# H-Bridge_Driver.net
KiCad netlist of a schematic drawn in Altium Designer
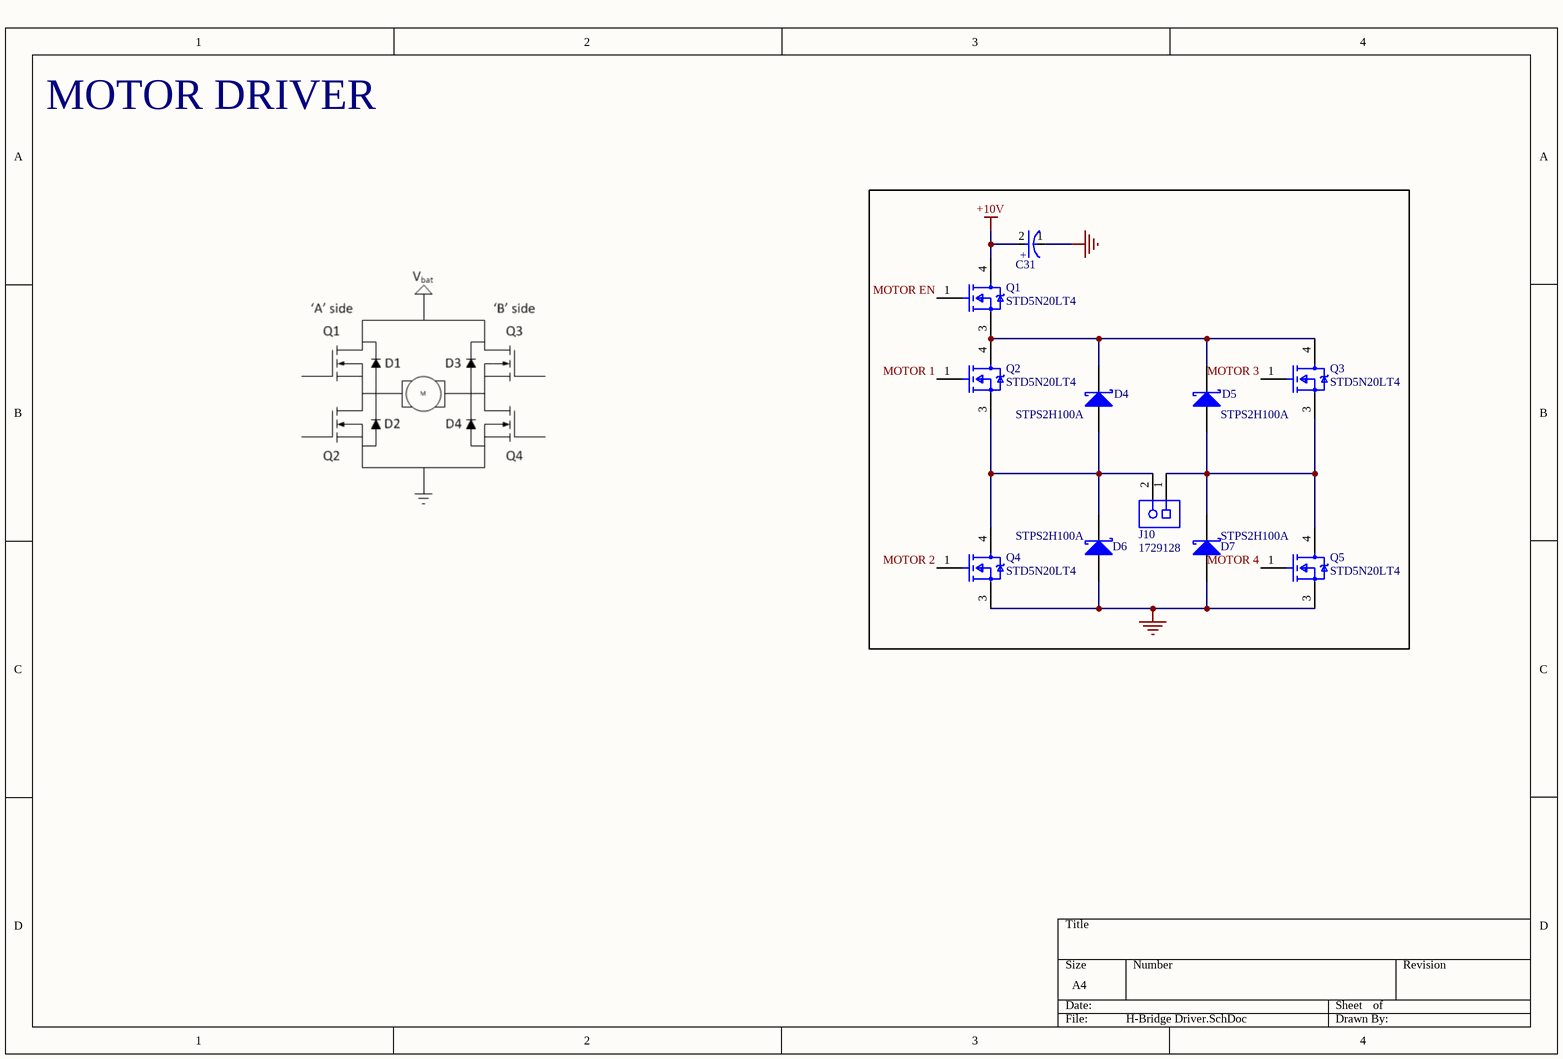
[diagram p0: H-Bridge Driver.SchDoc]

(export (version "E")
  (design (tool "Eeschema 10.0.6"))
  (components
    (comp (ref "C31")
      (value "EEE-1AA102P")
      (footprint "FP-SG-MFG")
      (fields (field (name "VOLTAGE") "10V") (field (name "TOLERANCE") "20%"))
      (libsource (lib "Altium Content Vault") (part "a00bbbee19879c290e62620ae7e47b1"))
    )
    (comp (ref "D4")
      (value "STPS2H100A")
      (footprint "STM-SMA-2_V")
      (description "Power Schottky Rectifier, 2 A, 100 V, 2-Pin SMD (SMA), RoHS, Tape and Reel")
      (fields (field (name "MANUFACTURER") "STMicroelectronics"))
      (libsource (lib "Altium Content Vault") (part "DSKY-AK-2"))
    )
    (comp (ref "D5")
      (value "STPS2H100A")
      (footprint "STM-SMA-2_V")
      (description "Power Schottky Rectifier, 2 A, 100 V, 2-Pin SMD (SMA), RoHS, Tape and Reel")
      (fields (field (name "MANUFACTURER") "STMicroelectronics"))
      (libsource (lib "Altium Content Vault") (part "DSKY-AK-2"))
    )
    (comp (ref "D6")
      (value "STPS2H100A")
      (footprint "STM-SMA-2_V")
      (description "Power Schottky Rectifier, 2 A, 100 V, 2-Pin SMD (SMA), RoHS, Tape and Reel")
      (fields (field (name "MANUFACTURER") "STMicroelectronics"))
      (libsource (lib "Altium Content Vault") (part "DSKY-AK-2"))
    )
    (comp (ref "D7")
      (value "STPS2H100A")
      (footprint "STM-SMA-2_V")
      (description "Power Schottky Rectifier, 2 A, 100 V, 2-Pin SMD (SMA), RoHS, Tape and Reel")
      (fields (field (name "MANUFACTURER") "STMicroelectronics"))
      (libsource (lib "Altium Content Vault") (part "DSKY-AK-2"))
    )
    (comp (ref "J10")
      (value "1729128")
      (footprint "PHOE-1729128-2_V")
      (description "PCB Terminal Block, 13.5 A, 400 V, 2-Pin THD, RoHS, Bulk")
      (fields (field (name "MANUFACTURER") "Phoenix Contact"))
      (libsource (lib "Altium Content Vault") (part "CN-2P-F-R2"))
    )
    (comp (ref "Q1")
      (value "STD5N20LT4")
      (footprint "FP-DPAK-P032P-MFG")
      (description "MOSFET N-CH 200V 5A DPAK")
      (fields
        (field (name "MANUFACTURER") "STMicroelectronics")
        (field (name "OCTOPART") "https://octopart.com/std5n20lt4-stmicroelectronics-335491")
      )
      (libsource (lib "Altium Content Vault") (part "cdf1c68f84cb049e5ebc85739c3fcf6"))
    )
    (comp (ref "Q2")
      (value "STD5N20LT4")
      (footprint "FP-DPAK-P032P-MFG")
      (description "MOSFET N-CH 200V 5A DPAK")
      (fields
        (field (name "MANUFACTURER") "STMicroelectronics")
        (field (name "OCTOPART") "https://octopart.com/std5n20lt4-stmicroelectronics-335491")
      )
      (libsource (lib "Altium Content Vault") (part "cdf1c68f84cb049e5ebc85739c3fcf6"))
    )
    (comp (ref "Q3")
      (value "STD5N20LT4")
      (footprint "FP-DPAK-P032P-MFG")
      (description "MOSFET N-CH 200V 5A DPAK")
      (fields
        (field (name "MANUFACTURER") "STMicroelectronics")
        (field (name "OCTOPART") "https://octopart.com/std5n20lt4-stmicroelectronics-335491")
      )
      (libsource (lib "Altium Content Vault") (part "cdf1c68f84cb049e5ebc85739c3fcf6"))
    )
    (comp (ref "Q4")
      (value "STD5N20LT4")
      (footprint "FP-DPAK-P032P-MFG")
      (description "MOSFET N-CH 200V 5A DPAK")
      (fields
        (field (name "MANUFACTURER") "STMicroelectronics")
        (field (name "OCTOPART") "https://octopart.com/std5n20lt4-stmicroelectronics-335491")
      )
      (libsource (lib "Altium Content Vault") (part "cdf1c68f84cb049e5ebc85739c3fcf6"))
    )
    (comp (ref "Q5")
      (value "STD5N20LT4")
      (footprint "FP-DPAK-P032P-MFG")
      (description "MOSFET N-CH 200V 5A DPAK")
      (fields
        (field (name "MANUFACTURER") "STMicroelectronics")
        (field (name "OCTOPART") "https://octopart.com/std5n20lt4-stmicroelectronics-335491")
      )
      (libsource (lib "Altium Content Vault") (part "cdf1c68f84cb049e5ebc85739c3fcf6"))
    )
  )
  (nets
    (net (code "1") (name "+10V") (class "Default")
      (node (ref "C31") (pin "2") (pinfunction "A_2") (pintype "passive"))
      (node (ref "Q1") (pin "4") (pinfunction "D_4") (pintype "passive"))
    )
    (net (code "2") (name "/MOTOR 1") (class "Default")
      (node (ref "Q2") (pin "1") (pinfunction "G_1") (pintype "passive"))
    )
    (net (code "3") (name "/MOTOR 2") (class "Default")
      (node (ref "Q4") (pin "1") (pinfunction "G_1") (pintype "passive"))
    )
    (net (code "4") (name "/MOTOR 3") (class "Default")
      (node (ref "Q3") (pin "1") (pinfunction "G_1") (pintype "passive"))
    )
    (net (code "5") (name "/MOTOR 4") (class "Default")
      (node (ref "Q5") (pin "1") (pinfunction "G_1") (pintype "passive"))
    )
    (net (code "6") (name "/MOTOR EN") (class "Default")
      (node (ref "Q1") (pin "1") (pinfunction "G_1") (pintype "passive"))
    )
    (net (code "7") (name "GND") (class "Default")
      (node (ref "C31") (pin "1") (pinfunction "C_1") (pintype "passive"))
      (node (ref "D6") (pin "1") (pinfunction "A_1") (pintype "passive"))
      (node (ref "D7") (pin "1") (pinfunction "A_1") (pintype "passive"))
      (node (ref "Q4") (pin "3") (pinfunction "S_3") (pintype "passive"))
      (node (ref "Q5") (pin "3") (pinfunction "S_3") (pintype "passive"))
    )
    (net (code "8") (name "Net-(D4-A)") (class "Default")
      (node (ref "D4") (pin "1") (pinfunction "A_1") (pintype "passive"))
      (node (ref "D6") (pin "2") (pinfunction "K_2") (pintype "passive"))
      (node (ref "J10") (pin "2") (pinfunction "2_2") (pintype "passive"))
      (node (ref "Q2") (pin "3") (pinfunction "S_3") (pintype "passive"))
      (node (ref "Q4") (pin "4") (pinfunction "D_4") (pintype "passive"))
    )
    (net (code "9") (name "Net-(D4-K)") (class "Default")
      (node (ref "D4") (pin "2") (pinfunction "K_2") (pintype "passive"))
      (node (ref "D5") (pin "2") (pinfunction "K_2") (pintype "passive"))
      (node (ref "Q1") (pin "3") (pinfunction "S_3") (pintype "passive"))
      (node (ref "Q2") (pin "4") (pinfunction "D_4") (pintype "passive"))
      (node (ref "Q3") (pin "4") (pinfunction "D_4") (pintype "passive"))
    )
    (net (code "10") (name "Net-(D5-A)") (class "Default")
      (node (ref "D5") (pin "1") (pinfunction "A_1") (pintype "passive"))
      (node (ref "D7") (pin "2") (pinfunction "K_2") (pintype "passive"))
      (node (ref "J10") (pin "1") (pinfunction "1_1") (pintype "passive"))
      (node (ref "Q3") (pin "3") (pinfunction "S_3") (pintype "passive"))
      (node (ref "Q5") (pin "4") (pinfunction "D_4") (pintype "passive"))
    )
  )
)
